# Hardware_Schematic.net
KiCad netlist of a schematic drawn in EAGLE
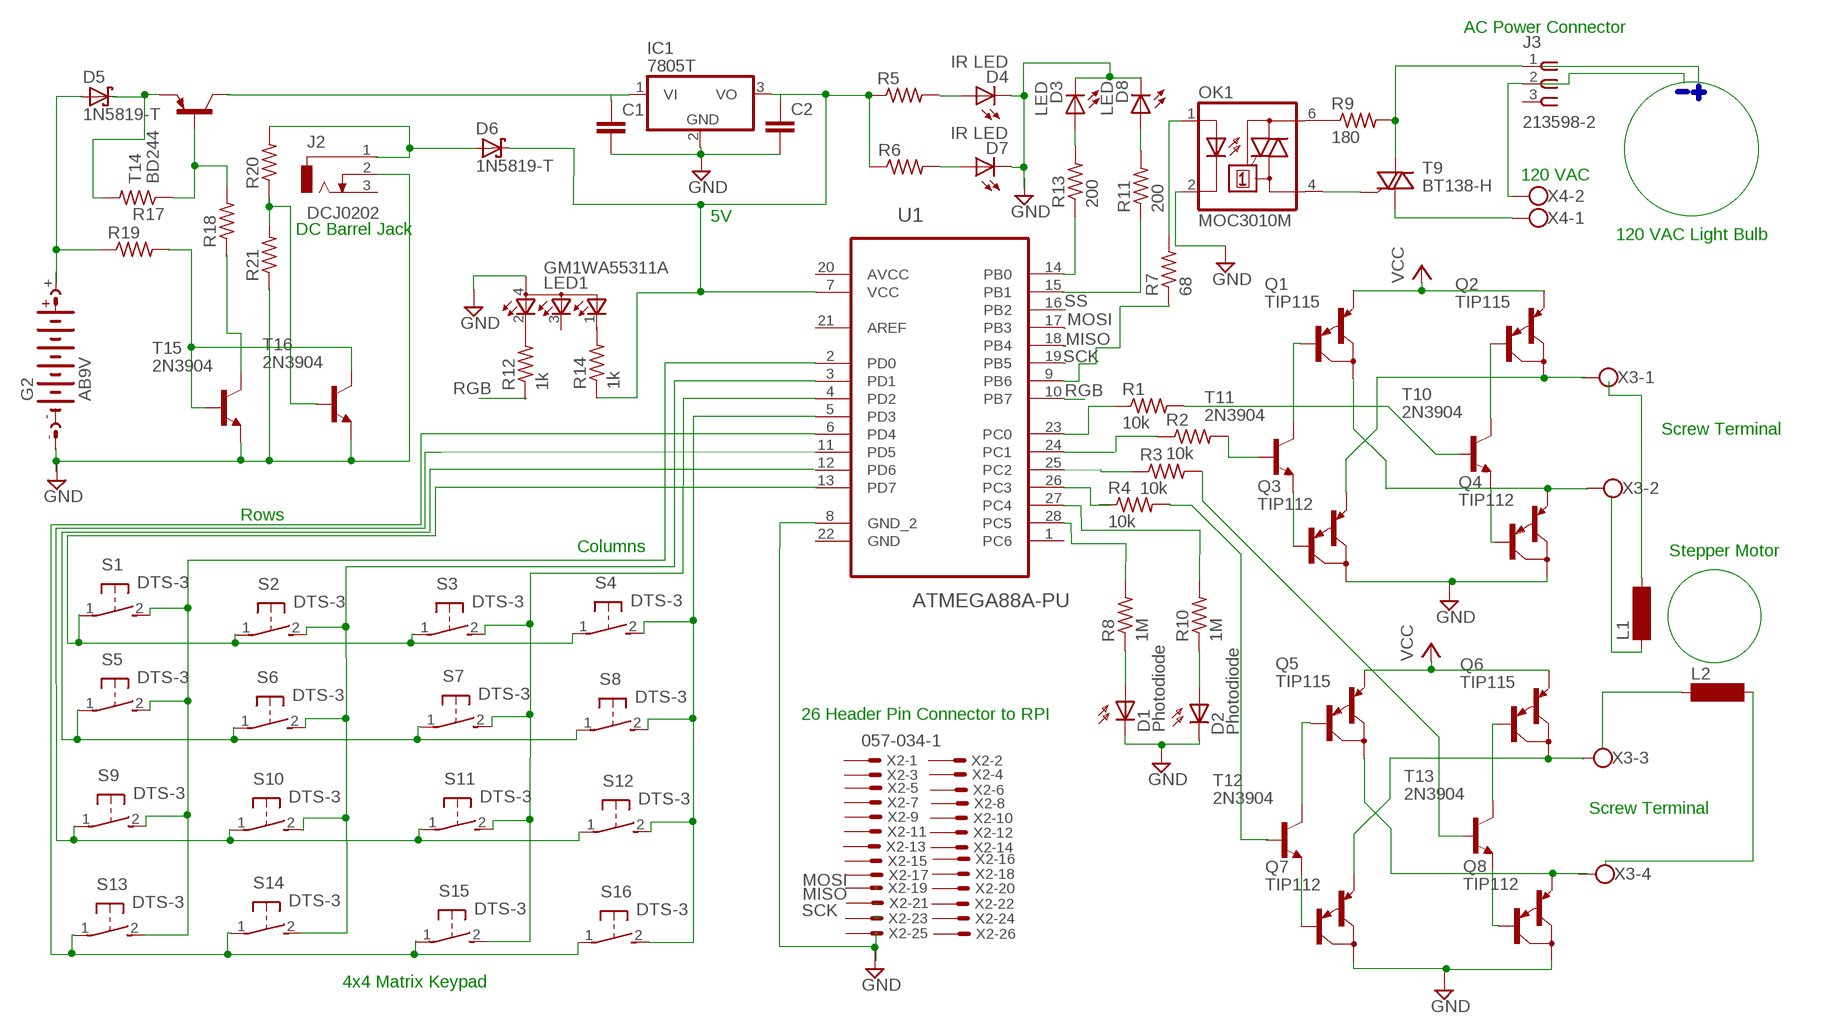
[diagram p0: schematic, sheet 1]

(export (version "E")
  (design (tool "Eeschema 10.0.6"))
  (components
    (comp (ref "C1")
      (value "C22/6")
      (footprint "eagle-import:C22.5B6")
      (libsource (lib "eagle-import") (part "C22/6"))
    )
    (comp (ref "C2")
      (value "C22/6")
      (footprint "eagle-import:C22.5B6")
      (libsource (lib "eagle-import") (part "C22/6"))
    )
    (comp (ref "D1")
      (value "Photodiode")
      (footprint "eagle-import:BPW32")
      (libsource (lib "eagle-import") (part "BPW32"))
    )
    (comp (ref "D2")
      (value "Photodiode")
      (footprint "eagle-import:BPW32")
      (libsource (lib "eagle-import") (part "BPW32"))
    )
    (comp (ref "D3")
      (value "LED")
      (footprint "eagle-import:SFH482")
      (libsource (lib "eagle-import") (part "SFH482"))
    )
    (comp (ref "D4")
      (value "IR LED")
      (footprint "eagle-import:SFH482")
      (libsource (lib "eagle-import") (part "SFH482"))
    )
    (comp (ref "D5")
      (value "1N5819-T")
      (footprint "eagle-import:DO41-7.6")
      (libsource (lib "eagle-import") (part "1N5819-T"))
    )
    (comp (ref "D6")
      (value "1N5819-T")
      (footprint "eagle-import:DO41-7.6")
      (libsource (lib "eagle-import") (part "1N5819-T"))
    )
    (comp (ref "D7")
      (value "IR LED")
      (footprint "eagle-import:SFH482")
      (libsource (lib "eagle-import") (part "SFH482"))
    )
    (comp (ref "D8")
      (value "LED")
      (footprint "eagle-import:SFH482")
      (libsource (lib "eagle-import") (part "SFH482"))
    )
    (comp (ref "G2")
      (value "AB9V")
      (footprint "eagle-import:AB9V")
      (libsource (lib "eagle-import") (part "AB9V"))
    )
    (comp (ref "IC1")
      (value "7805T")
      (footprint "eagle-import:TO220H")
      (libsource (lib "eagle-import") (part "78T05"))
    )
    (comp (ref "J2")
      (value "DCJ0202")
      (footprint "eagle-import:DCJ0202")
      (libsource (lib "eagle-import") (part "DCJ0202"))
    )
    (comp (ref "J3")
      (value "213598-2")
      (footprint "eagle-import:213598-2")
      (libsource (lib "eagle-import") (part "213598-2"))
    )
    (comp (ref "L1")
      (value "SM-Z15")
      (footprint "eagle-import:SM-Z15")
      (libsource (lib "eagle-import") (part "SM-Z15"))
    )
    (comp (ref "L2")
      (value "SM-Z15")
      (footprint "eagle-import:SM-Z15")
      (libsource (lib "eagle-import") (part "SM-Z15"))
    )
    (comp (ref "LED1")
      (value "GM1WA55311A")
      (footprint "eagle-import:GM1WA55311A")
      (libsource (lib "eagle-import") (part "GM1WA55311A"))
    )
    (comp (ref "OK1")
      (value "MOC3010M")
      (footprint "eagle-import:DIL06")
      (fields (field (name "MF") "FAIRCHILD SEMICONDUCTOR") (field (name "MPN") "MOC3010-M"))
      (libsource (lib "eagle-import") (part "MOC30M10"))
    )
    (comp (ref "Q1")
      (value "TIP115")
      (footprint "eagle-import:TO220")
      (libsource (lib "eagle-import") (part "TIP125"))
    )
    (comp (ref "Q2")
      (value "TIP115")
      (footprint "eagle-import:TO220")
      (libsource (lib "eagle-import") (part "TIP125"))
    )
    (comp (ref "Q3")
      (value "TIP112")
      (footprint "eagle-import:TO220")
      (libsource (lib "eagle-import") (part "TIP125"))
    )
    (comp (ref "Q4")
      (value "TIP112")
      (footprint "eagle-import:TO220")
      (libsource (lib "eagle-import") (part "TIP125"))
    )
    (comp (ref "Q5")
      (value "TIP115")
      (footprint "eagle-import:TO220")
      (libsource (lib "eagle-import") (part "TIP125"))
    )
    (comp (ref "Q6")
      (value "TIP115")
      (footprint "eagle-import:TO220")
      (libsource (lib "eagle-import") (part "TIP125"))
    )
    (comp (ref "Q7")
      (value "TIP112")
      (footprint "eagle-import:TO220")
      (libsource (lib "eagle-import") (part "TIP125"))
    )
    (comp (ref "Q8")
      (value "TIP112")
      (footprint "eagle-import:TO220")
      (libsource (lib "eagle-import") (part "TIP125"))
    )
    (comp (ref "R1")
      (value "10k")
      (footprint "eagle-import:0309V")
      (libsource (lib "eagle-import") (part "R-US_0309/V"))
    )
    (comp (ref "R2")
      (value "10k")
      (footprint "eagle-import:0309V")
      (libsource (lib "eagle-import") (part "R-US_0309/V"))
    )
    (comp (ref "R3")
      (value "10k")
      (footprint "eagle-import:0309V")
      (libsource (lib "eagle-import") (part "R-US_0309/V"))
    )
    (comp (ref "R4")
      (value "10k")
      (footprint "eagle-import:0309V")
      (libsource (lib "eagle-import") (part "R-US_0309/V"))
    )
    (comp (ref "R5")
      (value "R-US_0309/V")
      (footprint "eagle-import:0309V")
      (libsource (lib "eagle-import") (part "R-US_0309/V"))
    )
    (comp (ref "R6")
      (value "R-US_0309/V")
      (footprint "eagle-import:0309V")
      (libsource (lib "eagle-import") (part "R-US_0309/V"))
    )
    (comp (ref "R7")
      (value "68")
      (footprint "eagle-import:0309_12")
      (libsource (lib "eagle-import") (part "R-US_0309/12"))
    )
    (comp (ref "R8")
      (value "1M")
      (footprint "eagle-import:0309V")
      (libsource (lib "eagle-import") (part "R-US_0309/V"))
    )
    (comp (ref "R9")
      (value "180")
      (footprint "eagle-import:0309_12")
      (libsource (lib "eagle-import") (part "R-US_0309/12"))
    )
    (comp (ref "R10")
      (value "1M")
      (footprint "eagle-import:0309V")
      (libsource (lib "eagle-import") (part "R-US_0309/V"))
    )
    (comp (ref "R11")
      (value "200")
      (footprint "eagle-import:0309V")
      (libsource (lib "eagle-import") (part "R-US_0309/V"))
    )
    (comp (ref "R12")
      (value "1k")
      (footprint "eagle-import:0309V")
      (libsource (lib "eagle-import") (part "R-US_0309/V"))
    )
    (comp (ref "R13")
      (value "200")
      (footprint "eagle-import:0309V")
      (libsource (lib "eagle-import") (part "R-US_0309/V"))
    )
    (comp (ref "R14")
      (value "1k")
      (footprint "eagle-import:0309V")
      (libsource (lib "eagle-import") (part "R-US_0309/V"))
    )
    (comp (ref "R17")
      (value "R-US_0411/15")
      (footprint "eagle-import:0411_15")
      (libsource (lib "eagle-import") (part "R-US_0411/15"))
    )
    (comp (ref "R18")
      (value "R-US_0411/15")
      (footprint "eagle-import:0411_15")
      (libsource (lib "eagle-import") (part "R-US_0411/15"))
    )
    (comp (ref "R19")
      (value "R-US_0411/15")
      (footprint "eagle-import:0411_15")
      (libsource (lib "eagle-import") (part "R-US_0411/15"))
    )
    (comp (ref "R20")
      (value "R-US_0411/15")
      (footprint "eagle-import:0411_15")
      (libsource (lib "eagle-import") (part "R-US_0411/15"))
    )
    (comp (ref "R21")
      (value "R-US_0411/15")
      (footprint "eagle-import:0411_15")
      (libsource (lib "eagle-import") (part "R-US_0411/15"))
    )
    (comp (ref "S1")
      (value "DTS-3")
      (footprint "eagle-import:DTS-3")
      (libsource (lib "eagle-import") (part "DTS-3"))
    )
    (comp (ref "S2")
      (value "DTS-3")
      (footprint "eagle-import:DTS-3")
      (libsource (lib "eagle-import") (part "DTS-3"))
    )
    (comp (ref "S3")
      (value "DTS-3")
      (footprint "eagle-import:DTS-3")
      (libsource (lib "eagle-import") (part "DTS-3"))
    )
    (comp (ref "S4")
      (value "DTS-3")
      (footprint "eagle-import:DTS-3")
      (libsource (lib "eagle-import") (part "DTS-3"))
    )
    (comp (ref "S5")
      (value "DTS-3")
      (footprint "eagle-import:DTS-3")
      (libsource (lib "eagle-import") (part "DTS-3"))
    )
    (comp (ref "S6")
      (value "DTS-3")
      (footprint "eagle-import:DTS-3")
      (libsource (lib "eagle-import") (part "DTS-3"))
    )
    (comp (ref "S7")
      (value "DTS-3")
      (footprint "eagle-import:DTS-3")
      (libsource (lib "eagle-import") (part "DTS-3"))
    )
    (comp (ref "S8")
      (value "DTS-3")
      (footprint "eagle-import:DTS-3")
      (libsource (lib "eagle-import") (part "DTS-3"))
    )
    (comp (ref "S9")
      (value "DTS-3")
      (footprint "eagle-import:DTS-3")
      (libsource (lib "eagle-import") (part "DTS-3"))
    )
    (comp (ref "S10")
      (value "DTS-3")
      (footprint "eagle-import:DTS-3")
      (libsource (lib "eagle-import") (part "DTS-3"))
    )
    (comp (ref "S11")
      (value "DTS-3")
      (footprint "eagle-import:DTS-3")
      (libsource (lib "eagle-import") (part "DTS-3"))
    )
    (comp (ref "S12")
      (value "DTS-3")
      (footprint "eagle-import:DTS-3")
      (libsource (lib "eagle-import") (part "DTS-3"))
    )
    (comp (ref "S13")
      (value "DTS-3")
      (footprint "eagle-import:DTS-3")
      (libsource (lib "eagle-import") (part "DTS-3"))
    )
    (comp (ref "S14")
      (value "DTS-3")
      (footprint "eagle-import:DTS-3")
      (libsource (lib "eagle-import") (part "DTS-3"))
    )
    (comp (ref "S15")
      (value "DTS-3")
      (footprint "eagle-import:DTS-3")
      (libsource (lib "eagle-import") (part "DTS-3"))
    )
    (comp (ref "S16")
      (value "DTS-3")
      (footprint "eagle-import:DTS-3")
      (libsource (lib "eagle-import") (part "DTS-3"))
    )
    (comp (ref "T9")
      (value "BT138-H")
      (footprint "eagle-import:TO220BH")
      (libsource (lib "eagle-import") (part "BT138-H"))
    )
    (comp (ref "T10")
      (value "2N3904")
      (footprint "eagle-import:TO92")
      (libsource (lib "eagle-import") (part "2N3904"))
    )
    (comp (ref "T11")
      (value "2N3904")
      (footprint "eagle-import:TO92")
      (libsource (lib "eagle-import") (part "2N3904"))
    )
    (comp (ref "T12")
      (value "2N3904")
      (footprint "eagle-import:TO92")
      (libsource (lib "eagle-import") (part "2N3904"))
    )
    (comp (ref "T13")
      (value "2N3904")
      (footprint "eagle-import:TO92")
      (libsource (lib "eagle-import") (part "2N3904"))
    )
    (comp (ref "T14")
      (value "BD244")
      (footprint "eagle-import:TO220")
      (libsource (lib "eagle-import") (part "BD244"))
    )
    (comp (ref "T15")
      (value "2N3904")
      (footprint "eagle-import:TO92")
      (libsource (lib "eagle-import") (part "2N3904"))
    )
    (comp (ref "T16")
      (value "2N3904")
      (footprint "eagle-import:TO92")
      (libsource (lib "eagle-import") (part "2N3904"))
    )
    (comp (ref "U1")
      (value "ATMEGA88A-PU")
      (footprint "eagle-import:DIP254P762X457-28")
      (libsource (lib "eagle-import") (part "ATMEGA88A-PU"))
    )
    (comp (ref "X2")
      (value "057-034-1")
      (footprint "eagle-import:057-034-1")
      (libsource (lib "eagle-import") (part "057-034-1"))
    )
    (comp (ref "X3")
      (value "W237-4")
      (footprint "eagle-import:W237-4")
      (libsource (lib "eagle-import") (part "W237-4"))
    )
    (comp (ref "X4")
      (value "W237-102")
      (footprint "eagle-import:W237-102")
      (fields (field (name "MPN") "237-102"))
      (libsource (lib "eagle-import") (part "W237-102"))
    )
  )
  (nets
    (net (code "1") (name "/AVCC") (class "Default")
      (node (ref "U1") (pin "20") (pinfunction "AVCC_20") (pintype "power_in"))
    )
    (net (code "8") (name "Net-(R17-Pad1)") (class "Default")
      (node (ref "R17") (pin "1") (pinfunction "1_1") (pintype "passive"))
      (node (ref "R18") (pin "2") (pinfunction "2_2") (pintype "passive"))
    )
    (net (code "9") (name "Net-(T15-E)") (class "Default")
      (node (ref "J2") (pin "2") (pinfunction "2_2") (pintype "passive"))
      (node (ref "T15") (pin "3") (pinfunction "E_3") (pintype "passive"))
      (node (ref "T16") (pin "3") (pinfunction "E_3") (pintype "passive"))
    )
    (net (code "10") (name "VCC") (class "Default")
      (node (ref "U1") (pin "7") (pinfunction "VCC_7") (pintype "power_in"))
    )
    (net (code "11") (name "unconnected-(C1-Pad1)") (class "Default")
      (node (ref "C1") (pin "1") (pinfunction "1_1") (pintype "passive"))
    )
    (net (code "12") (name "unconnected-(C1-Pad2)") (class "Default")
      (node (ref "C1") (pin "2") (pinfunction "2_2") (pintype "passive"))
    )
    (net (code "13") (name "unconnected-(C2-Pad1)") (class "Default")
      (node (ref "C2") (pin "1") (pinfunction "1_1") (pintype "passive"))
    )
    (net (code "14") (name "unconnected-(C2-Pad2)") (class "Default")
      (node (ref "C2") (pin "2") (pinfunction "2_2") (pintype "passive"))
    )
    (net (code "15") (name "unconnected-(D1-C-PadK)") (class "Default")
      (node (ref "D1") (pin "K") (pinfunction "C_K") (pintype "passive"))
    )
    (net (code "16") (name "unconnected-(D1-PadA)") (class "Default")
      (node (ref "D1") (pin "A") (pinfunction "A_A") (pintype "passive"))
    )
    (net (code "17") (name "unconnected-(D2-C-PadK)") (class "Default")
      (node (ref "D2") (pin "K") (pinfunction "C_K") (pintype "passive"))
    )
    (net (code "18") (name "unconnected-(D2-PadA)") (class "Default")
      (node (ref "D2") (pin "A") (pinfunction "A_A") (pintype "passive"))
    )
    (net (code "19") (name "unconnected-(D3-C-PadK)") (class "Default")
      (node (ref "D3") (pin "K") (pinfunction "C_K") (pintype "passive"))
    )
    (net (code "20") (name "unconnected-(D3-PadA)") (class "Default")
      (node (ref "D3") (pin "A") (pinfunction "A_A") (pintype "passive"))
    )
    (net (code "21") (name "unconnected-(D4-C-PadK)") (class "Default")
      (node (ref "D4") (pin "K") (pinfunction "C_K") (pintype "passive"))
    )
    (net (code "22") (name "unconnected-(D4-PadA)") (class "Default")
      (node (ref "D4") (pin "A") (pinfunction "A_A") (pintype "passive"))
    )
    (net (code "23") (name "unconnected-(D5-PadA)") (class "Default")
      (node (ref "D5") (pin "A") (pinfunction "A_A") (pintype "passive"))
    )
    (net (code "24") (name "unconnected-(D5-PadC)") (class "Default")
      (node (ref "D5") (pin "C") (pinfunction "C_C") (pintype "passive"))
    )
    (net (code "25") (name "unconnected-(D6-PadA)") (class "Default")
      (node (ref "D6") (pin "A") (pinfunction "A_A") (pintype "passive"))
    )
    (net (code "26") (name "unconnected-(D6-PadC)") (class "Default")
      (node (ref "D6") (pin "C") (pinfunction "C_C") (pintype "passive"))
    )
    (net (code "27") (name "unconnected-(D7-C-PadK)") (class "Default")
      (node (ref "D7") (pin "K") (pinfunction "C_K") (pintype "passive"))
    )
    (net (code "28") (name "unconnected-(D7-PadA)") (class "Default")
      (node (ref "D7") (pin "A") (pinfunction "A_A") (pintype "passive"))
    )
    (net (code "29") (name "unconnected-(D8-C-PadK)") (class "Default")
      (node (ref "D8") (pin "K") (pinfunction "C_K") (pintype "passive"))
    )
    (net (code "30") (name "unconnected-(D8-PadA)") (class "Default")
      (node (ref "D8") (pin "A") (pinfunction "A_A") (pintype "passive"))
    )
    (net (code "31") (name "unconnected-(G2-Pad+)") (class "Default")
      (node (ref "G2") (pin "+") (pinfunction "+_+") (pintype "passive"))
    )
    (net (code "32") (name "unconnected-(G2-Pad-)") (class "Default")
      (node (ref "G2") (pin "-") (pinfunction "-_-") (pintype "passive"))
    )
    (net (code "33") (name "unconnected-(IC1-GND-Pad2)") (class "Default")
      (node (ref "IC1") (pin "2") (pinfunction "GND_2") (pintype "passive"))
    )
    (net (code "34") (name "unconnected-(IC1-VI-Pad1)") (class "Default")
      (node (ref "IC1") (pin "1") (pinfunction "VI_1") (pintype "input"))
    )
    (net (code "35") (name "unconnected-(IC1-VO-Pad3)") (class "Default")
      (node (ref "IC1") (pin "3") (pinfunction "VO_3") (pintype "passive"))
    )
    (net (code "36") (name "unconnected-(J2-Pad1)") (class "Default")
      (node (ref "J2") (pin "1") (pinfunction "1_1") (pintype "passive"))
    )
    (net (code "37") (name "unconnected-(J2-Pad3)") (class "Default")
      (node (ref "J2") (pin "3") (pinfunction "3_3") (pintype "passive"))
    )
    (net (code "38") (name "unconnected-(J3-Pad1)") (class "Default")
      (node (ref "J3") (pin "1") (pinfunction "1_1") (pintype "passive"))
    )
    (net (code "39") (name "unconnected-(J3-Pad2)") (class "Default")
      (node (ref "J3") (pin "2") (pinfunction "2_2") (pintype "passive"))
    )
    (net (code "40") (name "unconnected-(J3-Pad3)") (class "Default")
      (node (ref "J3") (pin "3") (pinfunction "3_3") (pintype "passive"))
    )
    (net (code "41") (name "unconnected-(L1-Pad1)") (class "Default")
      (node (ref "L1") (pin "1") (pinfunction "1_1") (pintype "passive"))
    )
    (net (code "42") (name "unconnected-(L1-Pad2)") (class "Default")
      (node (ref "L1") (pin "2") (pinfunction "2_2") (pintype "passive"))
    )
    (net (code "43") (name "unconnected-(L2-Pad1)") (class "Default")
      (node (ref "L2") (pin "1") (pinfunction "1_1") (pintype "passive"))
    )
    (net (code "44") (name "unconnected-(L2-Pad2)") (class "Default")
      (node (ref "L2") (pin "2") (pinfunction "2_2") (pintype "passive"))
    )
    (net (code "45") (name "unconnected-(LED1-A-Pad4)") (class "Default")
      (node (ref "LED1") (pin "4") (pinfunction "A_4") (pintype "passive"))
    )
    (net (code "46") (name "unconnected-(LED1-CBLUE-Pad3)") (class "Default")
      (node (ref "LED1") (pin "3") (pinfunction "CBLUE_3") (pintype "passive"))
    )
    (net (code "47") (name "unconnected-(LED1-CGREEN-Pad1)") (class "Default")
      (node (ref "LED1") (pin "1") (pinfunction "CGREEN_1") (pintype "passive"))
    )
    (net (code "48") (name "unconnected-(LED1-CRED-Pad2)") (class "Default")
      (node (ref "LED1") (pin "2") (pinfunction "CRED_2") (pintype "passive"))
    )
    (net (code "49") (name "unconnected-(OK1-A-Pad1)") (class "Default")
      (node (ref "OK1") (pin "1") (pinfunction "A_1") (pintype "passive"))
    )
    (net (code "50") (name "unconnected-(OK1-A1-Pad4)") (class "Default")
      (node (ref "OK1") (pin "4") (pinfunction "A1_4") (pintype "passive"))
    )
    (net (code "51") (name "unconnected-(OK1-A2-Pad6)") (class "Default")
      (node (ref "OK1") (pin "6") (pinfunction "A2_6") (pintype "passive"))
    )
    (net (code "52") (name "unconnected-(OK1-C-Pad2)") (class "Default")
      (node (ref "OK1") (pin "2") (pinfunction "C_2") (pintype "passive"))
    )
    (net (code "53") (name "unconnected-(Q1-B-Pad1)") (class "Default")
      (node (ref "Q1") (pin "1") (pinfunction "B_1") (pintype "passive"))
    )
    (net (code "54") (name "unconnected-(Q1-C-Pad2)") (class "Default")
      (node (ref "Q1") (pin "2") (pinfunction "C_2") (pintype "passive"))
    )
    (net (code "55") (name "unconnected-(Q1-E-Pad3)") (class "Default")
      (node (ref "Q1") (pin "3") (pinfunction "E_3") (pintype "passive"))
    )
    (net (code "56") (name "unconnected-(Q2-B-Pad1)") (class "Default")
      (node (ref "Q2") (pin "1") (pinfunction "B_1") (pintype "passive"))
    )
    (net (code "57") (name "unconnected-(Q2-C-Pad2)") (class "Default")
      (node (ref "Q2") (pin "2") (pinfunction "C_2") (pintype "passive"))
    )
    (net (code "58") (name "unconnected-(Q2-E-Pad3)") (class "Default")
      (node (ref "Q2") (pin "3") (pinfunction "E_3") (pintype "passive"))
    )
    (net (code "59") (name "unconnected-(Q3-B-Pad1)") (class "Default")
      (node (ref "Q3") (pin "1") (pinfunction "B_1") (pintype "passive"))
    )
    (net (code "60") (name "unconnected-(Q3-C-Pad2)") (class "Default")
      (node (ref "Q3") (pin "2") (pinfunction "C_2") (pintype "passive"))
    )
    (net (code "61") (name "unconnected-(Q3-E-Pad3)") (class "Default")
      (node (ref "Q3") (pin "3") (pinfunction "E_3") (pintype "passive"))
    )
    (net (code "62") (name "unconnected-(Q4-B-Pad1)") (class "Default")
      (node (ref "Q4") (pin "1") (pinfunction "B_1") (pintype "passive"))
    )
    (net (code "63") (name "unconnected-(Q4-C-Pad2)") (class "Default")
      (node (ref "Q4") (pin "2") (pinfunction "C_2") (pintype "passive"))
    )
    (net (code "64") (name "unconnected-(Q4-E-Pad3)") (class "Default")
      (node (ref "Q4") (pin "3") (pinfunction "E_3") (pintype "passive"))
    )
    (net (code "65") (name "unconnected-(Q5-B-Pad1)") (class "Default")
      (node (ref "Q5") (pin "1") (pinfunction "B_1") (pintype "passive"))
    )
    (net (code "66") (name "unconnected-(Q5-C-Pad2)") (class "Default")
      (node (ref "Q5") (pin "2") (pinfunction "C_2") (pintype "passive"))
    )
    (net (code "67") (name "unconnected-(Q5-E-Pad3)") (class "Default")
      (node (ref "Q5") (pin "3") (pinfunction "E_3") (pintype "passive"))
    )
    (net (code "68") (name "unconnected-(Q6-B-Pad1)") (class "Default")
      (node (ref "Q6") (pin "1") (pinfunction "B_1") (pintype "passive"))
    )
    (net (code "69") (name "unconnected-(Q6-C-Pad2)") (class "Default")
      (node (ref "Q6") (pin "2") (pinfunction "C_2") (pintype "passive"))
    )
    (net (code "70") (name "unconnected-(Q6-E-Pad3)") (class "Default")
      (node (ref "Q6") (pin "3") (pinfunction "E_3") (pintype "passive"))
    )
    (net (code "71") (name "unconnected-(Q7-B-Pad1)") (class "Default")
      (node (ref "Q7") (pin "1") (pinfunction "B_1") (pintype "passive"))
    )
    (net (code "72") (name "unconnected-(Q7-C-Pad2)") (class "Default")
      (node (ref "Q7") (pin "2") (pinfunction "C_2") (pintype "passive"))
    )
    (net (code "73") (name "unconnected-(Q7-E-Pad3)") (class "Default")
      (node (ref "Q7") (pin "3") (pinfunction "E_3") (pintype "passive"))
    )
    (net (code "74") (name "unconnected-(Q8-B-Pad1)") (class "Default")
      (node (ref "Q8") (pin "1") (pinfunction "B_1") (pintype "passive"))
    )
    (net (code "75") (name "unconnected-(Q8-C-Pad2)") (class "Default")
      (node (ref "Q8") (pin "2") (pinfunction "C_2") (pintype "passive"))
    )
    (net (code "76") (name "unconnected-(Q8-E-Pad3)") (class "Default")
      (node (ref "Q8") (pin "3") (pinfunction "E_3") (pintype "passive"))
    )
    (net (code "77") (name "unconnected-(R1-Pad1)") (class "Default")
      (node (ref "R1") (pin "1") (pinfunction "1_1") (pintype "passive"))
    )
    (net (code "78") (name "unconnected-(R1-Pad2)") (class "Default")
      (node (ref "R1") (pin "2") (pinfunction "2_2") (pintype "passive"))
    )
    (net (code "79") (name "unconnected-(R2-Pad1)") (class "Default")
      (node (ref "R2") (pin "1") (pinfunction "1_1") (pintype "passive"))
    )
    (net (code "80") (name "unconnected-(R2-Pad2)") (class "Default")
      (node (ref "R2") (pin "2") (pinfunction "2_2") (pintype "passive"))
    )
    (net (code "81") (name "unconnected-(R3-Pad1)") (class "Default")
      (node (ref "R3") (pin "1") (pinfunction "1_1") (pintype "passive"))
    )
    (net (code "82") (name "unconnected-(R3-Pad2)") (class "Default")
      (node (ref "R3") (pin "2") (pinfunction "2_2") (pintype "passive"))
    )
    (net (code "83") (name "unconnected-(R4-Pad1)") (class "Default")
      (node (ref "R4") (pin "1") (pinfunction "1_1") (pintype "passive"))
    )
    (net (code "84") (name "unconnected-(R4-Pad2)") (class "Default")
      (node (ref "R4") (pin "2") (pinfunction "2_2") (pintype "passive"))
    )
    (net (code "85") (name "unconnected-(R5-Pad1)") (class "Default")
      (node (ref "R5") (pin "1") (pinfunction "1_1") (pintype "passive"))
    )
    (net (code "86") (name "unconnected-(R5-Pad2)") (class "Default")
      (node (ref "R5") (pin "2") (pinfunction "2_2") (pintype "passive"))
    )
    (net (code "87") (name "unconnected-(R6-Pad1)") (class "Default")
      (node (ref "R6") (pin "1") (pinfunction "1_1") (pintype "passive"))
    )
    (net (code "88") (name "unconnected-(R6-Pad2)") (class "Default")
      (node (ref "R6") (pin "2") (pinfunction "2_2") (pintype "passive"))
    )
    (net (code "89") (name "unconnected-(R7-Pad1)") (class "Default")
      (node (ref "R7") (pin "1") (pinfunction "1_1") (pintype "passive"))
    )
    (net (code "90") (name "unconnected-(R7-Pad2)") (class "Default")
      (node (ref "R7") (pin "2") (pinfunction "2_2") (pintype "passive"))
    )
    (net (code "91") (name "unconnected-(R8-Pad1)") (class "Default")
      (node (ref "R8") (pin "1") (pinfunction "1_1") (pintype "passive"))
    )
    (net (code "92") (name "unconnected-(R8-Pad2)") (class "Default")
      (node (ref "R8") (pin "2") (pinfunction "2_2") (pintype "passive"))
    )
    (net (code "93") (name "unconnected-(R9-Pad1)") (class "Default")
      (node (ref "R9") (pin "1") (pinfunction "1_1") (pintype "passive"))
    )
    (net (code "94") (name "unconnected-(R9-Pad2)") (class "Default")
      (node (ref "R9") (pin "2") (pinfunction "2_2") (pintype "passive"))
    )
    (net (code "95") (name "unconnected-(R10-Pad1)") (class "Default")
      (node (ref "R10") (pin "1") (pinfunction "1_1") (pintype "passive"))
    )
    (net (code "96") (name "unconnected-(R10-Pad2)") (class "Default")
      (node (ref "R10") (pin "2") (pinfunction "2_2") (pintype "passive"))
    )
    (net (code "97") (name "unconnected-(R11-Pad1)") (class "Default")
      (node (ref "R11") (pin "1") (pinfunction "1_1") (pintype "passive"))
    )
    (net (code "98") (name "unconnected-(R11-Pad2)") (class "Default")
      (node (ref "R11") (pin "2") (pinfunction "2_2") (pintype "passive"))
    )
    (net (code "99") (name "unconnected-(R12-Pad1)") (class "Default")
      (node (ref "R12") (pin "1") (pinfunction "1_1") (pintype "passive"))
    )
    (net (code "100") (name "unconnected-(R12-Pad2)") (class "Default")
      (node (ref "R12") (pin "2") (pinfunction "2_2") (pintype "passive"))
    )
    (net (code "101") (name "unconnected-(R13-Pad1)") (class "Default")
      (node (ref "R13") (pin "1") (pinfunction "1_1") (pintype "passive"))
    )
    (net (code "102") (name "unconnected-(R13-Pad2)") (class "Default")
      (node (ref "R13") (pin "2") (pinfunction "2_2") (pintype "passive"))
    )
    (net (code "103") (name "unconnected-(R14-Pad1)") (class "Default")
      (node (ref "R14") (pin "1") (pinfunction "1_1") (pintype "passive"))
    )
    (net (code "104") (name "unconnected-(R14-Pad2)") (class "Default")
      (node (ref "R14") (pin "2") (pinfunction "2_2") (pintype "passive"))
    )
    (net (code "105") (name "unconnected-(R17-Pad2)") (class "Default")
      (node (ref "R17") (pin "2") (pinfunction "2_2") (pintype "passive"))
    )
    (net (code "106") (name "unconnected-(R18-Pad1)") (class "Default")
      (node (ref "R18") (pin "1") (pinfunction "1_1") (pintype "passive"))
    )
    (net (code "107") (name "unconnected-(R19-Pad1)") (class "Default")
      (node (ref "R19") (pin "1") (pinfunction "1_1") (pintype "passive"))
    )
    (net (code "108") (name "unconnected-(R19-Pad2)") (class "Default")
      (node (ref "R19") (pin "2") (pinfunction "2_2") (pintype "passive"))
    )
    (net (code "109") (name "unconnected-(R20-Pad1)") (class "Default")
      (node (ref "R20") (pin "1") (pinfunction "1_1") (pintype "passive"))
    )
    (net (code "110") (name "unconnected-(R20-Pad2)") (class "Default")
      (node (ref "R20") (pin "2") (pinfunction "2_2") (pintype "passive"))
    )
    (net (code "111") (name "unconnected-(R21-Pad1)") (class "Default")
      (node (ref "R21") (pin "1") (pinfunction "1_1") (pintype "passive"))
    )
    (net (code "112") (name "unconnected-(R21-Pad2)") (class "Default")
      (node (ref "R21") (pin "2") (pinfunction "2_2") (pintype "passive"))
    )
    (net (code "113") (name "unconnected-(S1-Pad1)") (class "Default")
      (node (ref "S1") (pin "1") (pinfunction "1_1") (pintype "passive"))
    )
    (net (code "114") (name "unconnected-(S1-Pad2)") (class "Default")
      (node (ref "S1") (pin "2") (pinfunction "2_2") (pintype "passive"))
    )
    (net (code "115") (name "unconnected-(S2-Pad1)") (class "Default")
      (node (ref "S2") (pin "1") (pinfunction "1_1") (pintype "passive"))
    )
    (net (code "116") (name "unconnected-(S2-Pad2)") (class "Default")
      (node (ref "S2") (pin "2") (pinfunction "2_2") (pintype "passive"))
    )
    (net (code "117") (name "unconnected-(S3-Pad1)") (class "Default")
      (node (ref "S3") (pin "1") (pinfunction "1_1") (pintype "passive"))
    )
    (net (code "118") (name "unconnected-(S3-Pad2)") (class "Default")
      (node (ref "S3") (pin "2") (pinfunction "2_2") (pintype "passive"))
    )
    (net (code "119") (name "unconnected-(S4-Pad1)") (class "Default")
      (node (ref "S4") (pin "1") (pinfunction "1_1") (pintype "passive"))
    )
    (net (code "120") (name "unconnected-(S4-Pad2)") (class "Default")
      (node (ref "S4") (pin "2") (pinfunction "2_2") (pintype "passive"))
    )
    (net (code "121") (name "unconnected-(S5-Pad1)") (class "Default")
      (node (ref "S5") (pin "1") (pinfunction "1_1") (pintype "passive"))
    )
    (net (code "122") (name "unconnected-(S5-Pad2)") (class "Default")
      (node (ref "S5") (pin "2") (pinfunction "2_2") (pintype "passive"))
    )
    (net (code "123") (name "unconnected-(S6-Pad1)") (class "Default")
      (node (ref "S6") (pin "1") (pinfunction "1_1") (pintype "passive"))
    )
    (net (code "124") (name "unconnected-(S6-Pad2)") (class "Default")
      (node (ref "S6") (pin "2") (pinfunction "2_2") (pintype "passive"))
    )
    (net (code "125") (name "unconnected-(S7-Pad1)") (class "Default")
      (node (ref "S7") (pin "1") (pinfunction "1_1") (pintype "passive"))
    )
    (net (code "126") (name "unconnected-(S7-Pad2)") (class "Default")
      (node (ref "S7") (pin "2") (pinfunction "2_2") (pintype "passive"))
    )
    (net (code "127") (name "unconnected-(S8-Pad1)") (class "Default")
      (node (ref "S8") (pin "1") (pinfunction "1_1") (pintype "passive"))
    )
    (net (code "128") (name "unconnected-(S8-Pad2)") (class "Default")
      (node (ref "S8") (pin "2") (pinfunction "2_2") (pintype "passive"))
    )
    (net (code "129") (name "unconnected-(S9-Pad1)") (class "Default")
      (node (ref "S9") (pin "1") (pinfunction "1_1") (pintype "passive"))
    )
    (net (code "130") (name "unconnected-(S9-Pad2)") (class "Default")
      (node (ref "S9") (pin "2") (pinfunction "2_2") (pintype "passive"))
    )
    (net (code "131") (name "unconnected-(S10-Pad1)") (class "Default")
      (node (ref "S10") (pin "1") (pinfunction "1_1") (pintype "passive"))
    )
    (net (code "132") (name "unconnected-(S10-Pad2)") (class "Default")
      (node (ref "S10") (pin "2") (pinfunction "2_2") (pintype "passive"))
    )
    (net (code "133") (name "unconnected-(S11-Pad1)") (class "Default")
      (node (ref "S11") (pin "1") (pinfunction "1_1") (pintype "passive"))
    )
    (net (code "134") (name "unconnected-(S11-Pad2)") (class "Default")
      (node (ref "S11") (pin "2") (pinfunction "2_2") (pintype "passive"))
    )
    (net (code "135") (name "unconnected-(S12-Pad1)") (class "Default")
      (node (ref "S12") (pin "1") (pinfunction "1_1") (pintype "passive"))
    )
    (net (code "136") (name "unconnected-(S12-Pad2)") (class "Default")
      (node (ref "S12") (pin "2") (pinfunction "2_2") (pintype "passive"))
    )
    (net (code "137") (name "unconnected-(S13-Pad1)") (class "Default")
      (node (ref "S13") (pin "1") (pinfunction "1_1") (pintype "passive"))
    )
    (net (code "138") (name "unconnected-(S13-Pad2)") (class "Default")
      (node (ref "S13") (pin "2") (pinfunction "2_2") (pintype "passive"))
    )
    (net (code "139") (name "unconnected-(S14-Pad1)") (class "Default")
      (node (ref "S14") (pin "1") (pinfunction "1_1") (pintype "passive"))
    )
    (net (code "140") (name "unconnected-(S14-Pad2)") (class "Default")
      (node (ref "S14") (pin "2") (pinfunction "2_2") (pintype "passive"))
    )
    (net (code "141") (name "unconnected-(S15-Pad1)") (class "Default")
      (node (ref "S15") (pin "1") (pinfunction "1_1") (pintype "passive"))
    )
    (net (code "142") (name "unconnected-(S15-Pad2)") (class "Default")
      (node (ref "S15") (pin "2") (pinfunction "2_2") (pintype "passive"))
    )
    (net (code "143") (name "unconnected-(S16-Pad1)") (class "Default")
      (node (ref "S16") (pin "1") (pinfunction "1_1") (pintype "passive"))
    )
    (net (code "144") (name "unconnected-(S16-Pad2)") (class "Default")
      (node (ref "S16") (pin "2") (pinfunction "2_2") (pintype "passive"))
    )
    (net (code "145") (name "unconnected-(T9-A1-PadT1)") (class "Default")
      (node (ref "T9") (pin "T1") (pinfunction "A1_T1") (pintype "passive"))
    )
    (net (code "146") (name "unconnected-(T9-A2-PadT2)") (class "Default")
      (node (ref "T9") (pin "T2") (pinfunction "A2_T2") (pintype "passive"))
    )
    (net (code "147") (name "unconnected-(T9-PadG)") (class "Default")
      (node (ref "T9") (pin "G") (pinfunction "G_G") (pintype "passive"))
    )
    (net (code "148") (name "unconnected-(T10-B-Pad2)") (class "Default")
      (node (ref "T10") (pin "2") (pinfunction "B_2") (pintype "passive"))
    )
    (net (code "149") (name "unconnected-(T10-C-Pad1)") (class "Default")
      (node (ref "T10") (pin "1") (pinfunction "C_1") (pintype "passive"))
    )
    (net (code "150") (name "unconnected-(T10-E-Pad3)") (class "Default")
      (node (ref "T10") (pin "3") (pinfunction "E_3") (pintype "passive"))
    )
    (net (code "151") (name "unconnected-(T11-B-Pad2)") (class "Default")
      (node (ref "T11") (pin "2") (pinfunction "B_2") (pintype "passive"))
    )
    (net (code "152") (name "unconnected-(T11-C-Pad1)") (class "Default")
      (node (ref "T11") (pin "1") (pinfunction "C_1") (pintype "passive"))
    )
    (net (code "153") (name "unconnected-(T11-E-Pad3)") (class "Default")
      (node (ref "T11") (pin "3") (pinfunction "E_3") (pintype "passive"))
    )
    (net (code "154") (name "unconnected-(T12-B-Pad2)") (class "Default")
      (node (ref "T12") (pin "2") (pinfunction "B_2") (pintype "passive"))
    )
    (net (code "155") (name "unconnected-(T12-C-Pad1)") (class "Default")
      (node (ref "T12") (pin "1") (pinfunction "C_1") (pintype "passive"))
    )
    (net (code "156") (name "unconnected-(T12-E-Pad3)") (class "Default")
      (node (ref "T12") (pin "3") (pinfunction "E_3") (pintype "passive"))
    )
    (net (code "157") (name "unconnected-(T13-B-Pad2)") (class "Default")
      (node (ref "T13") (pin "2") (pinfunction "B_2") (pintype "passive"))
    )
    (net (code "158") (name "unconnected-(T13-C-Pad1)") (class "Default")
      (node (ref "T13") (pin "1") (pinfunction "C_1") (pintype "passive"))
    )
    (net (code "159") (name "unconnected-(T13-E-Pad3)") (class "Default")
      (node (ref "T13") (pin "3") (pinfunction "E_3") (pintype "passive"))
    )
    (net (code "160") (name "unconnected-(T14-B-Pad1)") (class "Default")
      (node (ref "T14") (pin "1") (pinfunction "B_1") (pintype "passive"))
    )
    (net (code "161") (name "unconnected-(T14-C-Pad2)") (class "Default")
      (node (ref "T14") (pin "2") (pinfunction "C_2") (pintype "passive"))
    )
    (net (code "162") (name "unconnected-(T14-E-Pad3)") (class "Default")
      (node (ref "T14") (pin "3") (pinfunction "E_3") (pintype "passive"))
    )
    (net (code "163") (name "unconnected-(T15-B-Pad2)") (class "Default")
      (node (ref "T15") (pin "2") (pinfunction "B_2") (pintype "passive"))
    )
    (net (code "164") (name "unconnected-(T15-C-Pad1)") (class "Default")
      (node (ref "T15") (pin "1") (pinfunction "C_1") (pintype "passive"))
    )
    (net (code "165") (name "unconnected-(T16-B-Pad2)") (class "Default")
      (node (ref "T16") (pin "2") (pinfunction "B_2") (pintype "passive"))
    )
    (net (code "166") (name "unconnected-(T16-C-Pad1)") (class "Default")
      (node (ref "T16") (pin "1") (pinfunction "C_1") (pintype "passive"))
    )
    (net (code "167") (name "unconnected-(U1-AREF-Pad21)") (class "Default")
      (node (ref "U1") (pin "21") (pinfunction "AREF_21") (pintype "input"))
    )
    (net (code "168") (name "unconnected-(U1-GND-Pad22)") (class "Default")
      (node (ref "U1") (pin "22") (pinfunction "GND_22") (pintype "passive"))
    )
    (net (code "169") (name "unconnected-(U1-GND_2-Pad8)") (class "Default")
      (node (ref "U1") (pin "8") (pinfunction "GND_2_8") (pintype "passive"))
    )
    (net (code "170") (name "unconnected-(U1-PB0-Pad14)") (class "Default")
      (node (ref "U1") (pin "14") (pinfunction "PB0_14") (pintype "bidirectional"))
    )
    (net (code "171") (name "unconnected-(U1-PB1-Pad15)") (class "Default")
      (node (ref "U1") (pin "15") (pinfunction "PB1_15") (pintype "bidirectional"))
    )
    (net (code "172") (name "unconnected-(U1-PB2-Pad16)") (class "Default")
      (node (ref "U1") (pin "16") (pinfunction "PB2_16") (pintype "bidirectional"))
    )
    (net (code "173") (name "unconnected-(U1-PB3-Pad17)") (class "Default")
      (node (ref "U1") (pin "17") (pinfunction "PB3_17") (pintype "bidirectional"))
    )
    (net (code "174") (name "unconnected-(U1-PB4-Pad18)") (class "Default")
      (node (ref "U1") (pin "18") (pinfunction "PB4_18") (pintype "bidirectional"))
    )
    (net (code "175") (name "unconnected-(U1-PB5-Pad19)") (class "Default")
      (node (ref "U1") (pin "19") (pinfunction "PB5_19") (pintype "bidirectional"))
    )
    (net (code "176") (name "unconnected-(U1-PB6-Pad9)") (class "Default")
      (node (ref "U1") (pin "9") (pinfunction "PB6_9") (pintype "bidirectional"))
    )
    (net (code "177") (name "unconnected-(U1-PB7-Pad10)") (class "Default")
      (node (ref "U1") (pin "10") (pinfunction "PB7_10") (pintype "bidirectional"))
    )
    (net (code "178") (name "unconnected-(U1-PC0-Pad23)") (class "Default")
      (node (ref "U1") (pin "23") (pinfunction "PC0_23") (pintype "bidirectional"))
    )
    (net (code "179") (name "unconnected-(U1-PC1-Pad24)") (class "Default")
      (node (ref "U1") (pin "24") (pinfunction "PC1_24") (pintype "bidirectional"))
    )
    (net (code "180") (name "unconnected-(U1-PC2-Pad25)") (class "Default")
      (node (ref "U1") (pin "25") (pinfunction "PC2_25") (pintype "bidirectional"))
    )
    (net (code "181") (name "unconnected-(U1-PC3-Pad26)") (class "Default")
      (node (ref "U1") (pin "26") (pinfunction "PC3_26") (pintype "bidirectional"))
    )
    (net (code "182") (name "unconnected-(U1-PC4-Pad27)") (class "Default")
      (node (ref "U1") (pin "27") (pinfunction "PC4_27") (pintype "bidirectional"))
    )
    (net (code "183") (name "unconnected-(U1-PC5-Pad28)") (class "Default")
      (node (ref "U1") (pin "28") (pinfunction "PC5_28") (pintype "bidirectional"))
    )
    (net (code "184") (name "unconnected-(U1-PC6-Pad1)") (class "Default")
      (node (ref "U1") (pin "1") (pinfunction "PC6_1") (pintype "bidirectional"))
    )
    (net (code "185") (name "unconnected-(U1-PD0-Pad2)") (class "Default")
      (node (ref "U1") (pin "2") (pinfunction "PD0_2") (pintype "bidirectional"))
    )
    (net (code "186") (name "unconnected-(U1-PD1-Pad3)") (class "Default")
      (node (ref "U1") (pin "3") (pinfunction "PD1_3") (pintype "bidirectional"))
    )
    (net (code "187") (name "unconnected-(U1-PD2-Pad4)") (class "Default")
      (node (ref "U1") (pin "4") (pinfunction "PD2_4") (pintype "bidirectional"))
    )
    (net (code "188") (name "unconnected-(U1-PD3-Pad5)") (class "Default")
      (node (ref "U1") (pin "5") (pinfunction "PD3_5") (pintype "bidirectional"))
    )
    (net (code "189") (name "unconnected-(U1-PD4-Pad6)") (class "Default")
      (node (ref "U1") (pin "6") (pinfunction "PD4_6") (pintype "bidirectional"))
    )
    (net (code "190") (name "unconnected-(U1-PD5-Pad11)") (class "Default")
      (node (ref "U1") (pin "11") (pinfunction "PD5_11") (pintype "bidirectional"))
    )
    (net (code "191") (name "unconnected-(U1-PD6-Pad12)") (class "Default")
      (node (ref "U1") (pin "12") (pinfunction "PD6_12") (pintype "bidirectional"))
    )
    (net (code "192") (name "unconnected-(U1-PD7-Pad13)") (class "Default")
      (node (ref "U1") (pin "13") (pinfunction "PD7_13") (pintype "bidirectional"))
    )
    (net (code "193") (name "unconnected-(X2A-S-Pad1)") (class "Default")
      (node (ref "X2") (pin "1") (pinfunction "S_1") (pintype "passive"))
    )
    (net (code "194") (name "unconnected-(X2AC-S-Pad4)") (class "Default")
      (node (ref "X2") (pin "4") (pinfunction "S_4") (pintype "passive"))
    )
    (net (code "195") (name "unconnected-(X2AD-S-Pad5)") (class "Default")
      (node (ref "X2") (pin "5") (pinfunction "S_5") (pintype "passive"))
    )
    (net (code "196") (name "unconnected-(X2AE-S-Pad6)") (class "Default")
      (node (ref "X2") (pin "6") (pinfunction "S_6") (pintype "passive"))
    )
    (net (code "197") (name "unconnected-(X2AF-S-Pad7)") (class "Default")
      (node (ref "X2") (pin "7") (pinfunction "S_7") (pintype "passive"))
    )
    (net (code "198") (name "unconnected-(X2AG-S-Pad8)") (class "Default")
      (node (ref "X2") (pin "8") (pinfunction "S_8") (pintype "passive"))
    )
    (net (code "199") (name "unconnected-(X2AH-S-Pad9)") (class "Default")
      (node (ref "X2") (pin "9") (pinfunction "S_9") (pintype "passive"))
    )
    (net (code "200") (name "unconnected-(X2B-S-Pad10)") (class "Default")
      (node (ref "X2") (pin "10") (pinfunction "S_10") (pintype "passive"))
    )
    (net (code "201") (name "unconnected-(X2C-S-Pad11)") (class "Default")
      (node (ref "X2") (pin "11") (pinfunction "S_11") (pintype "passive"))
    )
    (net (code "202") (name "unconnected-(X2D-S-Pad12)") (class "Default")
      (node (ref "X2") (pin "12") (pinfunction "S_12") (pintype "passive"))
    )
    (net (code "203") (name "unconnected-(X2E-S-Pad13)") (class "Default")
      (node (ref "X2") (pin "13") (pinfunction "S_13") (pintype "passive"))
    )
    (net (code "204") (name "unconnected-(X2F-S-Pad14)") (class "Default")
      (node (ref "X2") (pin "14") (pinfunction "S_14") (pintype "passive"))
    )
    (net (code "205") (name "unconnected-(X2G-S-Pad15)") (class "Default")
      (node (ref "X2") (pin "15") (pinfunction "S_15") (pintype "passive"))
    )
    (net (code "206") (name "unconnected-(X2H-S-Pad16)") (class "Default")
      (node (ref "X2") (pin "16") (pinfunction "S_16") (pintype "passive"))
    )
    (net (code "207") (name "unconnected-(X2I-S-Pad17)") (class "Default")
      (node (ref "X2") (pin "17") (pinfunction "S_17") (pintype "passive"))
    )
    (net (code "208") (name "unconnected-(X2J-S-Pad18)") (class "Default")
      (node (ref "X2") (pin "18") (pinfunction "S_18") (pintype "passive"))
    )
    (net (code "209") (name "unconnected-(X2K-S-Pad19)") (class "Default")
      (node (ref "X2") (pin "19") (pinfunction "S_19") (pintype "passive"))
    )
    (net (code "210") (name "unconnected-(X2L-S-Pad2)") (class "Default")
      (node (ref "X2") (pin "2") (pinfunction "S_2") (pintype "passive"))
    )
    (net (code "211") (name "unconnected-(X2M-S-Pad20)") (class "Default")
      (node (ref "X2") (pin "20") (pinfunction "S_20") (pintype "passive"))
    )
    (net (code "212") (name "unconnected-(X2N-S-Pad21)") (class "Default")
      (node (ref "X2") (pin "21") (pinfunction "S_21") (pintype "passive"))
    )
    (net (code "213") (name "unconnected-(X2O-S-Pad22)") (class "Default")
      (node (ref "X2") (pin "22") (pinfunction "S_22") (pintype "passive"))
    )
    (net (code "214") (name "unconnected-(X2P-S-Pad23)") (class "Default")
      (node (ref "X2") (pin "23") (pinfunction "S_23") (pintype "passive"))
    )
    (net (code "215") (name "unconnected-(X2Q-S-Pad24)") (class "Default")
      (node (ref "X2") (pin "24") (pinfunction "S_24") (pintype "passive"))
    )
    (net (code "216") (name "unconnected-(X2R-S-Pad25)") (class "Default")
      (node (ref "X2") (pin "25") (pinfunction "S_25") (pintype "passive"))
    )
    (net (code "217") (name "unconnected-(X2S-S-Pad26)") (class "Default")
      (node (ref "X2") (pin "26") (pinfunction "S_26") (pintype "passive"))
    )
    (net (code "218") (name "unconnected-(X2W-S-Pad3)") (class "Default")
      (node (ref "X2") (pin "3") (pinfunction "S_3") (pintype "passive"))
    )
    (net (code "219") (name "unconnected-(X3A-KL-Pad1)") (class "Default")
      (node (ref "X3") (pin "1") (pinfunction "KL_1") (pintype "passive"))
    )
    (net (code "220") (name "unconnected-(X3B-KL-Pad2)") (class "Default")
      (node (ref "X3") (pin "2") (pinfunction "KL_2") (pintype "passive"))
    )
    (net (code "221") (name "unconnected-(X3C-KL-Pad3)") (class "Default")
      (node (ref "X3") (pin "3") (pinfunction "KL_3") (pintype "passive"))
    )
    (net (code "222") (name "unconnected-(X3D-KL-Pad4)") (class "Default")
      (node (ref "X3") (pin "4") (pinfunction "KL_4") (pintype "passive"))
    )
    (net (code "223") (name "unconnected-(X4A-KL-Pad1)") (class "Default")
      (node (ref "X4") (pin "1") (pinfunction "KL_1") (pintype "passive"))
    )
    (net (code "224") (name "unconnected-(X4B-KL-Pad2)") (class "Default")
      (node (ref "X4") (pin "2") (pinfunction "KL_2") (pintype "passive"))
    )
  )
)
